# usbMIDI2CV_MC.net
KiCad netlist of a schematic drawn in EAGLE
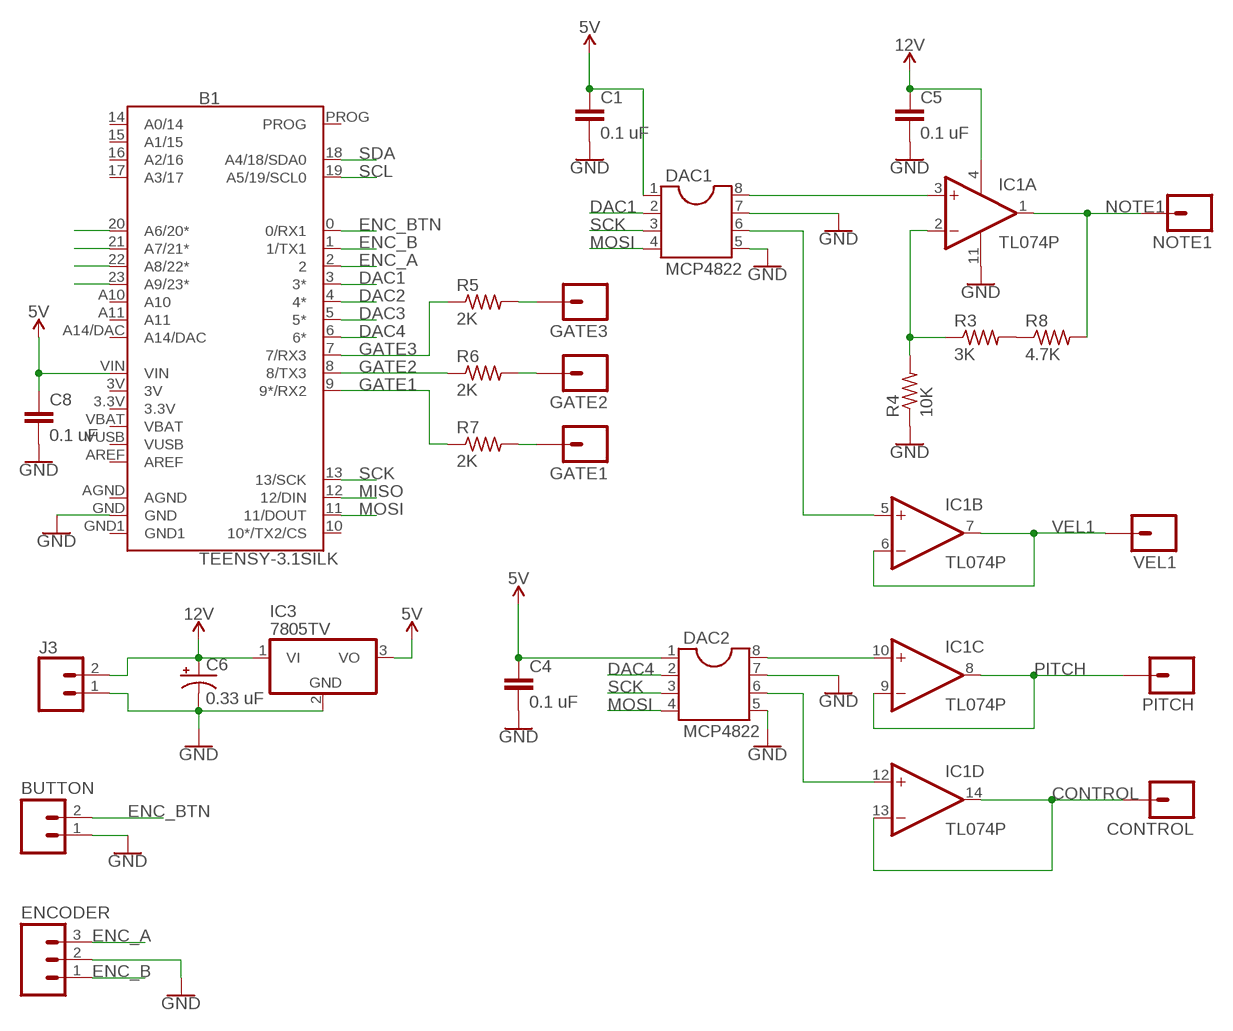
[diagram p0: schematic, sheet 1]

(export (version "E")
  (design (tool "Eeschema 10.0.6"))
  (components
    (comp (ref "B1")
      (value "TEENSY-3.1SILK")
      (footprint "eagle-import:TEENSY-3.1")
      (libsource (lib "eagle-import") (part "TEENSY-3.1SILK"))
    )
    (comp (ref "BUTTON")
      (value "M02LOCK_LONGPADS")
      (footprint "eagle-import:1X02_LOCK_LONGPADS")
      (libsource (lib "eagle-import") (part "M02LOCK_LONGPADS"))
    )
    (comp (ref "C1")
      (value "0.1 uF")
      (footprint "eagle-import:CAP-PTH-SMALL")
      (libsource (lib "eagle-import") (part "CAPPTH"))
    )
    (comp (ref "C4")
      (value "0.1 uF")
      (footprint "eagle-import:CAP-PTH-SMALL")
      (libsource (lib "eagle-import") (part "CAPPTH"))
    )
    (comp (ref "C5")
      (value "0.1 uF")
      (footprint "eagle-import:CAP-PTH-SMALL")
      (libsource (lib "eagle-import") (part "CAPPTH"))
    )
    (comp (ref "C6")
      (value "0.33 uF")
      (footprint "eagle-import:CPOL-RADIAL-100UF-25V")
      (libsource (lib "eagle-import") (part "CAP_POLPTH1"))
    )
    (comp (ref "C8")
      (value "0.1 uF")
      (footprint "eagle-import:CAP-PTH-SMALL")
      (libsource (lib "eagle-import") (part "CAPPTH"))
    )
    (comp (ref "CONTROL")
      (value "M01PTH_NO_SILK_YES_STOP")
      (footprint "eagle-import:1X01_NO_SILK")
      (libsource (lib "eagle-import") (part "M01PTH_NO_SILK_YES_STOP"))
    )
    (comp (ref "DAC1")
      (value "MCP4822")
      (footprint "eagle-import:SOCKET-08")
      (fields (field (name "SPICEPREFIX") "X"))
      (libsource (lib "eagle-import") (part "DIL8S"))
    )
    (comp (ref "DAC2")
      (value "MCP4822")
      (footprint "eagle-import:SOCKET-08")
      (fields (field (name "SPICEPREFIX") "X"))
      (libsource (lib "eagle-import") (part "DIL8S"))
    )
    (comp (ref "ENCODER")
      (value "M03LONGPADS")
      (footprint "eagle-import:1X03_LONGPADS")
      (libsource (lib "eagle-import") (part "M03LONGPADS"))
    )
    (comp (ref "GATE1")
      (value "M01PTH_NO_SILK_YES_STOP")
      (footprint "eagle-import:1X01_NO_SILK")
      (libsource (lib "eagle-import") (part "M01PTH_NO_SILK_YES_STOP"))
    )
    (comp (ref "GATE2")
      (value "M01PTH_NO_SILK_YES_STOP")
      (footprint "eagle-import:1X01_NO_SILK")
      (libsource (lib "eagle-import") (part "M01PTH_NO_SILK_YES_STOP"))
    )
    (comp (ref "GATE3")
      (value "M01PTH_NO_SILK_YES_STOP")
      (footprint "eagle-import:1X01_NO_SILK")
      (libsource (lib "eagle-import") (part "M01PTH_NO_SILK_YES_STOP"))
    )
    (comp (ref "IC1")
      (value "TL074P")
      (footprint "eagle-import:DIL14")
      (libsource (lib "eagle-import") (part "TL074P"))
    )
    (comp (ref "IC3")
      (value "7805TV")
      (footprint "eagle-import:TO220V")
      (libsource (lib "eagle-import") (part "78TV05"))
    )
    (comp (ref "J3")
      (value "CONN_025MM")
      (footprint "eagle-import:SCREWTERMINAL-5MM-2")
      (libsource (lib "eagle-import") (part "CONN_025MM"))
    )
    (comp (ref "NOTE1")
      (value "M01PTH_NO_SILK_YES_STOP")
      (footprint "eagle-import:1X01_NO_SILK")
      (libsource (lib "eagle-import") (part "M01PTH_NO_SILK_YES_STOP"))
    )
    (comp (ref "PITCH")
      (value "M01PTH_NO_SILK_YES_STOP")
      (footprint "eagle-import:1X01_NO_SILK")
      (libsource (lib "eagle-import") (part "M01PTH_NO_SILK_YES_STOP"))
    )
    (comp (ref "R3")
      (value "3K")
      (footprint "eagle-import:0207_10")
      (libsource (lib "eagle-import") (part "R-US_0207/10"))
    )
    (comp (ref "R4")
      (value "10K")
      (footprint "eagle-import:0207_10")
      (libsource (lib "eagle-import") (part "R-US_0207/10"))
    )
    (comp (ref "R5")
      (value "2K")
      (footprint "eagle-import:0207_10")
      (libsource (lib "eagle-import") (part "R-US_0207/10"))
    )
    (comp (ref "R6")
      (value "2K")
      (footprint "eagle-import:0207_10")
      (libsource (lib "eagle-import") (part "R-US_0207/10"))
    )
    (comp (ref "R7")
      (value "2K")
      (footprint "eagle-import:0207_10")
      (libsource (lib "eagle-import") (part "R-US_0207/10"))
    )
    (comp (ref "R8")
      (value "4.7K")
      (footprint "eagle-import:0207_10")
      (libsource (lib "eagle-import") (part "R-US_0207/10"))
    )
    (comp (ref "VEL1")
      (value "M01PTH_NO_SILK_YES_STOP")
      (footprint "eagle-import:1X01_NO_SILK")
      (libsource (lib "eagle-import") (part "M01PTH_NO_SILK_YES_STOP"))
    )
  )
  (nets
    (net (code "1") (name "/3.3V") (class "Default")
      (node (ref "B1") (pin "3.3V") (pinfunction "3.3V_3.3V") (pintype "power_in"))
    )
    (net (code "2") (name "/3V") (class "Default")
      (node (ref "B1") (pin "3V") (pinfunction "3V_3V") (pintype "power_in"))
    )
    (net (code "3") (name "/AGND") (class "Default")
      (node (ref "B1") (pin "AGND") (pinfunction "AGND_AGND") (pintype "power_in"))
    )
    (net (code "4") (name "/CONTROL") (class "Default")
      (node (ref "CONTROL") (pin "1") (pinfunction "1_1") (pintype "passive"))
      (node (ref "IC1") (pin "13") (pinfunction "-IN_13") (pintype "input"))
      (node (ref "IC1") (pin "14") (pinfunction "OUT_14") (pintype "output"))
    )
    (net (code "5") (name "/DAC1") (class "Default")
      (node (ref "B1") (pin "3") (pinfunction "3*_3") (pintype "bidirectional"))
      (node (ref "DAC1") (pin "2") (pinfunction "2_2") (pintype "passive"))
    )
    (net (code "6") (name "/DAC2") (class "Default")
      (node (ref "B1") (pin "4") (pinfunction "4*_4") (pintype "bidirectional"))
    )
    (net (code "7") (name "/DAC3") (class "Default")
      (node (ref "B1") (pin "5") (pinfunction "5*_5") (pintype "bidirectional"))
    )
    (net (code "8") (name "/DAC4") (class "Default")
      (node (ref "B1") (pin "6") (pinfunction "6*_6") (pintype "bidirectional"))
      (node (ref "DAC2") (pin "2") (pinfunction "2_2") (pintype "passive"))
    )
    (net (code "9") (name "/ENC_A") (class "Default")
      (node (ref "B1") (pin "2") (pinfunction "2_2") (pintype "bidirectional"))
      (node (ref "ENCODER") (pin "3") (pinfunction "3_3") (pintype "passive"))
    )
    (net (code "10") (name "/ENC_B") (class "Default")
      (node (ref "B1") (pin "1") (pinfunction "1/TX1_1") (pintype "bidirectional"))
      (node (ref "ENCODER") (pin "1") (pinfunction "1_1") (pintype "passive"))
    )
    (net (code "11") (name "/ENC_BTN") (class "Default")
      (node (ref "B1") (pin "0") (pinfunction "0/RX1_0") (pintype "bidirectional"))
      (node (ref "BUTTON") (pin "2") (pinfunction "2_2") (pintype "passive"))
    )
    (net (code "12") (name "/GATE1") (class "Default")
      (node (ref "B1") (pin "9") (pinfunction "9*/RX2_9") (pintype "bidirectional"))
      (node (ref "R7") (pin "1") (pinfunction "1_1") (pintype "passive"))
    )
    (net (code "13") (name "/GATE2") (class "Default")
      (node (ref "B1") (pin "8") (pinfunction "8/TX3_8") (pintype "bidirectional"))
      (node (ref "R6") (pin "1") (pinfunction "1_1") (pintype "passive"))
    )
    (net (code "14") (name "/GATE3") (class "Default")
      (node (ref "B1") (pin "7") (pinfunction "7/RX3_7") (pintype "bidirectional"))
      (node (ref "R5") (pin "1") (pinfunction "1_1") (pintype "passive"))
    )
    (net (code "15") (name "/GND1") (class "Default")
      (node (ref "B1") (pin "GND1") (pinfunction "GND1_GND1") (pintype "power_in"))
    )
    (net (code "16") (name "/MISO") (class "Default")
      (node (ref "B1") (pin "12") (pinfunction "12/DIN_12") (pintype "bidirectional"))
    )
    (net (code "17") (name "/MOSI") (class "Default")
      (node (ref "B1") (pin "11") (pinfunction "11/DOUT_11") (pintype "bidirectional"))
      (node (ref "DAC1") (pin "4") (pinfunction "4_4") (pintype "passive"))
      (node (ref "DAC2") (pin "4") (pinfunction "4_4") (pintype "passive"))
    )
    (net (code "18") (name "/NOTE1") (class "Default")
      (node (ref "IC1") (pin "1") (pinfunction "OUT_1") (pintype "output"))
      (node (ref "NOTE1") (pin "1") (pinfunction "1_1") (pintype "passive"))
      (node (ref "R8") (pin "2") (pinfunction "2_2") (pintype "passive"))
    )
    (net (code "19") (name "/PITCH") (class "Default")
      (node (ref "IC1") (pin "8") (pinfunction "OUT_8") (pintype "output"))
      (node (ref "IC1") (pin "9") (pinfunction "-IN_9") (pintype "input"))
      (node (ref "PITCH") (pin "1") (pinfunction "1_1") (pintype "passive"))
    )
    (net (code "20") (name "/SCK") (class "Default")
      (node (ref "B1") (pin "13") (pinfunction "13/SCK_13") (pintype "bidirectional"))
      (node (ref "DAC1") (pin "3") (pinfunction "3_3") (pintype "passive"))
      (node (ref "DAC2") (pin "3") (pinfunction "3_3") (pintype "passive"))
    )
    (net (code "21") (name "/SCL") (class "Default")
      (node (ref "B1") (pin "19") (pinfunction "A5/19/SCL0_19") (pintype "bidirectional"))
    )
    (net (code "22") (name "/SDA") (class "Default")
      (node (ref "B1") (pin "18") (pinfunction "A4/18/SDA0_18") (pintype "bidirectional"))
    )
    (net (code "23") (name "/VBAT") (class "Default")
      (node (ref "B1") (pin "VBAT") (pinfunction "VBAT_VBAT") (pintype "power_in"))
    )
    (net (code "24") (name "/VEL1") (class "Default")
      (node (ref "IC1") (pin "6") (pinfunction "-IN_6") (pintype "input"))
      (node (ref "IC1") (pin "7") (pinfunction "OUT_7") (pintype "output"))
      (node (ref "VEL1") (pin "1") (pinfunction "1_1") (pintype "passive"))
    )
    (net (code "25") (name "/VUSB") (class "Default")
      (node (ref "B1") (pin "VUSB") (pinfunction "VUSB_VUSB") (pintype "power_in"))
    )
    (net (code "26") (name "5V") (class "Default")
      (node (ref "B1") (pin "VIN") (pinfunction "VIN_VIN") (pintype "power_in"))
      (node (ref "C1") (pin "1") (pinfunction "1_1") (pintype "passive"))
      (node (ref "C4") (pin "1") (pinfunction "1_1") (pintype "passive"))
      (node (ref "C8") (pin "1") (pinfunction "1_1") (pintype "passive"))
      (node (ref "DAC1") (pin "1") (pinfunction "1_1") (pintype "passive"))
      (node (ref "DAC2") (pin "1") (pinfunction "1_1") (pintype "passive"))
      (node (ref "IC3") (pin "3") (pinfunction "VO_3") (pintype "passive"))
    )
    (net (code "27") (name "12V") (class "Default")
      (node (ref "C5") (pin "1") (pinfunction "1_1") (pintype "passive"))
      (node (ref "C6") (pin "1") (pinfunction "+_1") (pintype "passive"))
      (node (ref "IC1") (pin "4") (pinfunction "V+_4") (pintype "power_in"))
      (node (ref "IC3") (pin "1") (pinfunction "VI_1") (pintype "input"))
      (node (ref "J3") (pin "2") (pinfunction "2_2") (pintype "passive"))
    )
    (net (code "28") (name "GND") (class "Default")
      (node (ref "B1") (pin "GND") (pinfunction "GND_GND") (pintype "power_in"))
      (node (ref "BUTTON") (pin "1") (pinfunction "1_1") (pintype "passive"))
      (node (ref "C1") (pin "2") (pinfunction "2_2") (pintype "passive"))
      (node (ref "C4") (pin "2") (pinfunction "2_2") (pintype "passive"))
      (node (ref "C5") (pin "2") (pinfunction "2_2") (pintype "passive"))
      (node (ref "C6") (pin "2") (pinfunction "-_2") (pintype "passive"))
      (node (ref "C8") (pin "2") (pinfunction "2_2") (pintype "passive"))
      (node (ref "DAC1") (pin "5") (pinfunction "5_5") (pintype "passive"))
      (node (ref "DAC1") (pin "7") (pinfunction "7_7") (pintype "passive"))
      (node (ref "DAC2") (pin "5") (pinfunction "5_5") (pintype "passive"))
      (node (ref "DAC2") (pin "7") (pinfunction "7_7") (pintype "passive"))
      (node (ref "ENCODER") (pin "2") (pinfunction "2_2") (pintype "passive"))
      (node (ref "IC1") (pin "11") (pinfunction "V-_11") (pintype "power_in"))
      (node (ref "IC3") (pin "2") (pinfunction "GND_2") (pintype "passive"))
      (node (ref "J3") (pin "1") (pinfunction "1_1") (pintype "passive"))
      (node (ref "R4") (pin "1") (pinfunction "1_1") (pintype "passive"))
    )
    (net (code "29") (name "Net-(GATE1-Pad1)") (class "Default")
      (node (ref "GATE1") (pin "1") (pinfunction "1_1") (pintype "passive"))
      (node (ref "R7") (pin "2") (pinfunction "2_2") (pintype "passive"))
    )
    (net (code "30") (name "Net-(GATE2-Pad1)") (class "Default")
      (node (ref "GATE2") (pin "1") (pinfunction "1_1") (pintype "passive"))
      (node (ref "R6") (pin "2") (pinfunction "2_2") (pintype "passive"))
    )
    (net (code "31") (name "Net-(GATE3-Pad1)") (class "Default")
      (node (ref "GATE3") (pin "1") (pinfunction "1_1") (pintype "passive"))
      (node (ref "R5") (pin "2") (pinfunction "2_2") (pintype "passive"))
    )
    (net (code "32") (name "Net-(IC1A-+IN)") (class "Default")
      (node (ref "DAC1") (pin "8") (pinfunction "8_8") (pintype "passive"))
      (node (ref "IC1") (pin "3") (pinfunction "+IN_3") (pintype "input"))
    )
    (net (code "33") (name "Net-(IC1A--IN)") (class "Default")
      (node (ref "IC1") (pin "2") (pinfunction "-IN_2") (pintype "input"))
      (node (ref "R3") (pin "1") (pinfunction "1_1") (pintype "passive"))
      (node (ref "R4") (pin "2") (pinfunction "2_2") (pintype "passive"))
    )
    (net (code "34") (name "Net-(IC1B-+IN)") (class "Default")
      (node (ref "DAC1") (pin "6") (pinfunction "6_6") (pintype "passive"))
      (node (ref "IC1") (pin "5") (pinfunction "+IN_5") (pintype "input"))
    )
    (net (code "35") (name "Net-(IC1C-+IN)") (class "Default")
      (node (ref "DAC2") (pin "8") (pinfunction "8_8") (pintype "passive"))
      (node (ref "IC1") (pin "10") (pinfunction "+IN_10") (pintype "input"))
    )
    (net (code "36") (name "Net-(IC1D-+IN)") (class "Default")
      (node (ref "DAC2") (pin "6") (pinfunction "6_6") (pintype "passive"))
      (node (ref "IC1") (pin "12") (pinfunction "+IN_12") (pintype "input"))
    )
    (net (code "37") (name "Net-(R3-Pad2)") (class "Default")
      (node (ref "R3") (pin "2") (pinfunction "2_2") (pintype "passive"))
      (node (ref "R8") (pin "1") (pinfunction "1_1") (pintype "passive"))
    )
    (net (code "38") (name "unconnected-(B1-10*{slash}TX2{slash}CS-Pad10)") (class "Default")
      (node (ref "B1") (pin "10") (pinfunction "10*/TX2/CS_10") (pintype "bidirectional"))
    )
    (net (code "39") (name "unconnected-(B1-A0{slash}14-Pad14)") (class "Default")
      (node (ref "B1") (pin "14") (pinfunction "A0/14_14") (pintype "bidirectional"))
    )
    (net (code "40") (name "unconnected-(B1-A1{slash}15-Pad15)") (class "Default")
      (node (ref "B1") (pin "15") (pinfunction "A1/15_15") (pintype "bidirectional"))
    )
    (net (code "41") (name "unconnected-(B1-A2{slash}16-Pad16)") (class "Default")
      (node (ref "B1") (pin "16") (pinfunction "A2/16_16") (pintype "bidirectional"))
    )
    (net (code "42") (name "unconnected-(B1-A3{slash}17-Pad17)") (class "Default")
      (node (ref "B1") (pin "17") (pinfunction "A3/17_17") (pintype "bidirectional"))
    )
    (net (code "43") (name "unconnected-(B1-A6{slash}20*-Pad20)") (class "Default")
      (node (ref "B1") (pin "20") (pinfunction "A6/20*_20") (pintype "bidirectional"))
    )
    (net (code "44") (name "unconnected-(B1-A7{slash}21*-Pad21)") (class "Default")
      (node (ref "B1") (pin "21") (pinfunction "A7/21*_21") (pintype "bidirectional"))
    )
    (net (code "45") (name "unconnected-(B1-A8{slash}22*-Pad22)") (class "Default")
      (node (ref "B1") (pin "22") (pinfunction "A8/22*_22") (pintype "bidirectional"))
    )
    (net (code "46") (name "unconnected-(B1-A9{slash}23*-Pad23)") (class "Default")
      (node (ref "B1") (pin "23") (pinfunction "A9/23*_23") (pintype "bidirectional"))
    )
    (net (code "47") (name "unconnected-(B1-PadA10)") (class "Default")
      (node (ref "B1") (pin "A10") (pinfunction "A10_A10") (pintype "bidirectional"))
    )
    (net (code "48") (name "unconnected-(B1-PadA11)") (class "Default")
      (node (ref "B1") (pin "A11") (pinfunction "A11_A11") (pintype "bidirectional"))
    )
    (net (code "49") (name "unconnected-(B1-PadA14{slash}DAC)") (class "Default")
      (node (ref "B1") (pin "A14/DAC") (pinfunction "A14/DAC_A14/DAC") (pintype "bidirectional"))
    )
    (net (code "50") (name "unconnected-(B1-PadAREF)") (class "Default")
      (node (ref "B1") (pin "AREF") (pinfunction "AREF_AREF") (pintype "bidirectional"))
    )
    (net (code "51") (name "unconnected-(B1-PadPROG)") (class "Default")
      (node (ref "B1") (pin "PROG") (pinfunction "PROG_PROG") (pintype "bidirectional"))
    )
  )
)
